# AQ_sensor_GSM.net
KiCad netlist of a schematic drawn in EAGLE
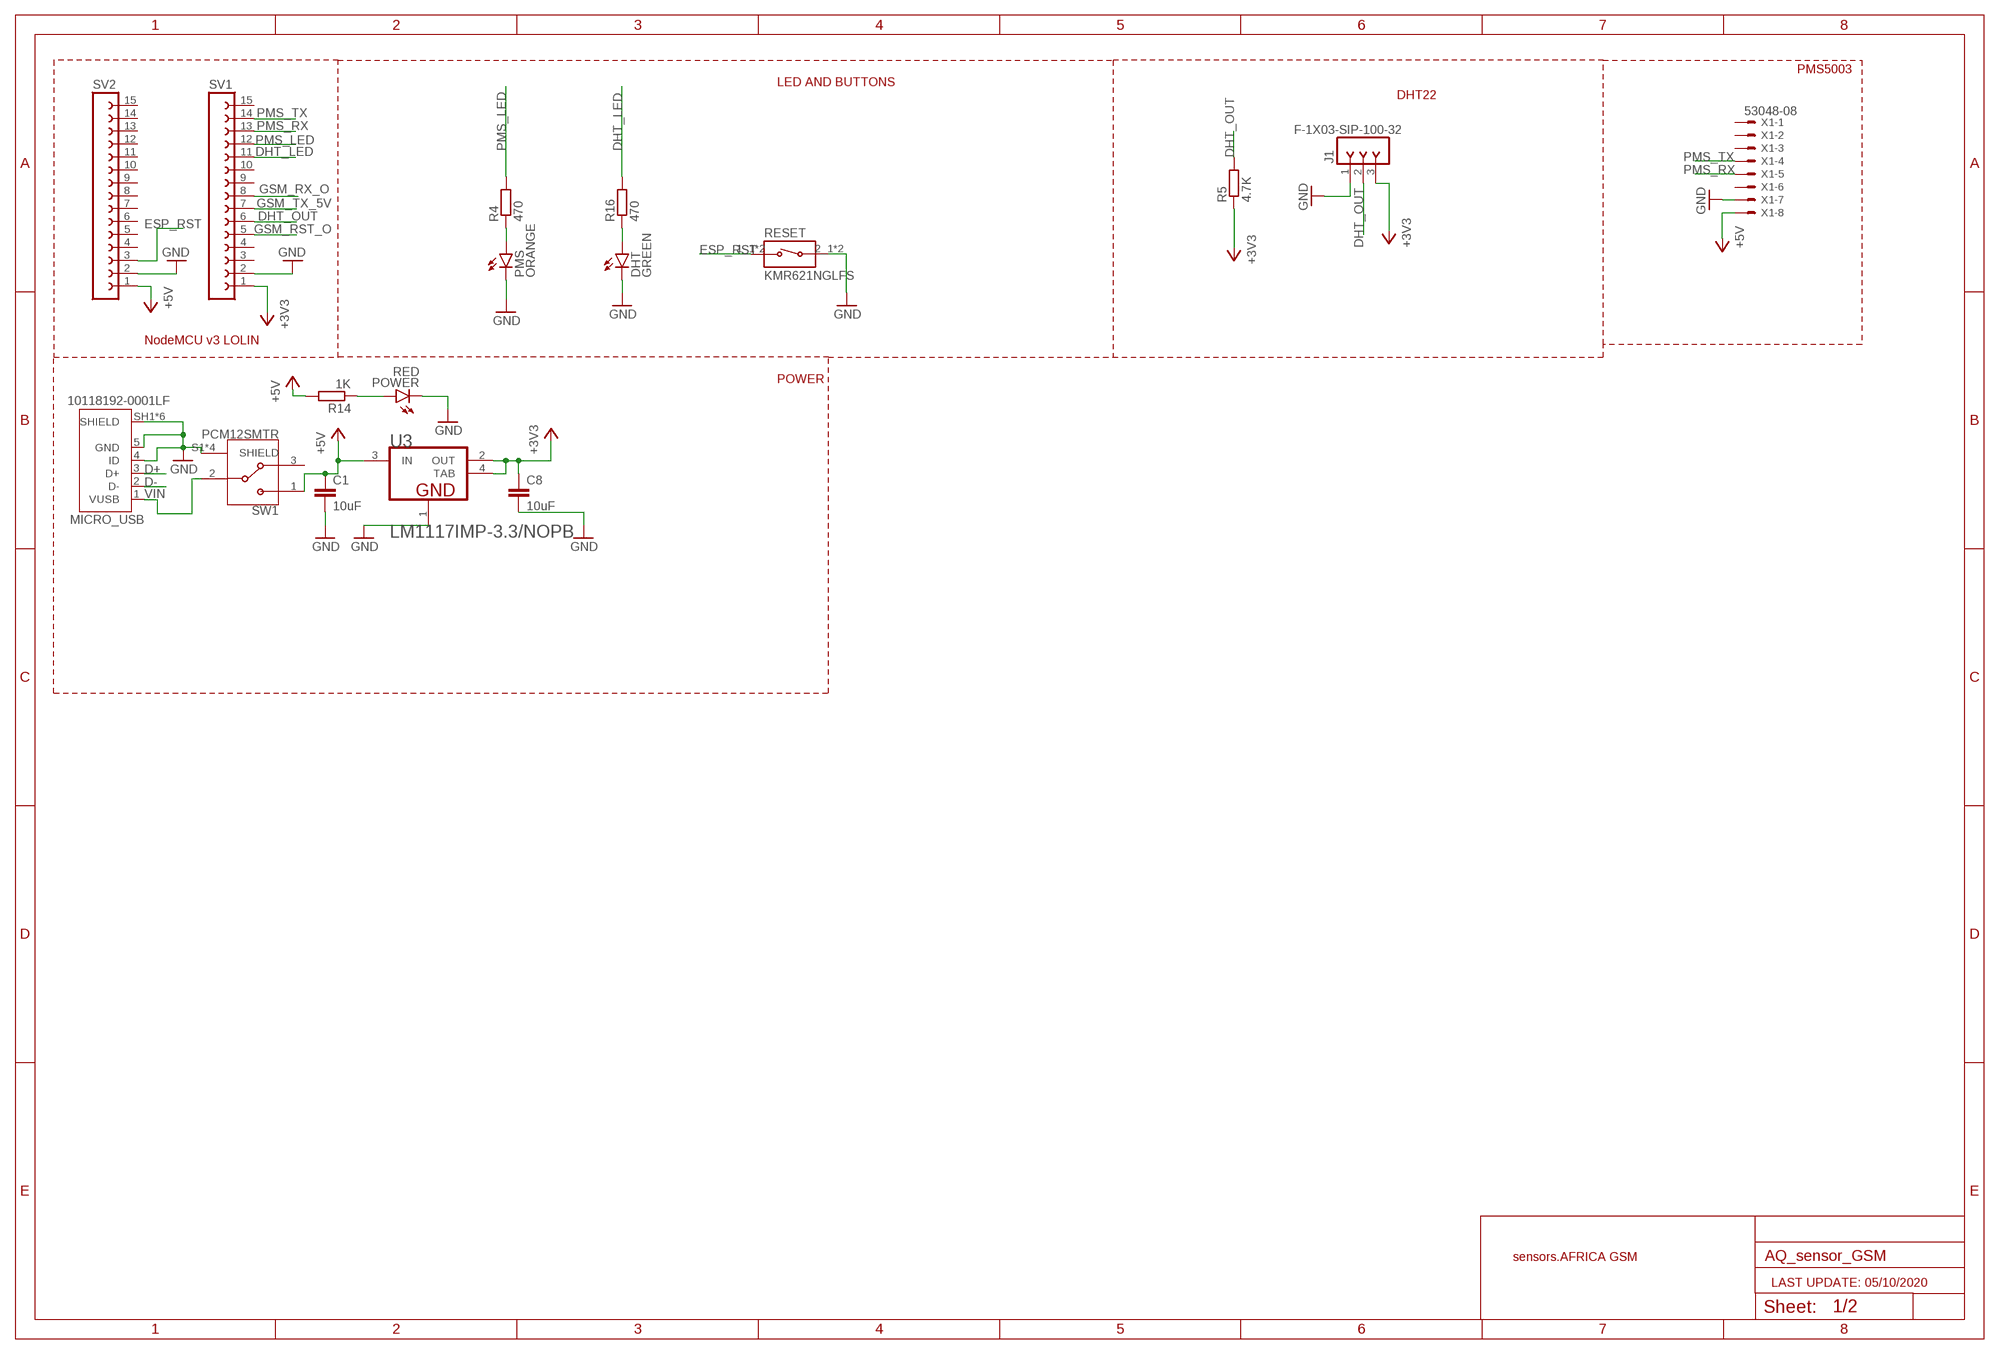
[diagram p0: schematic, sheet 1]
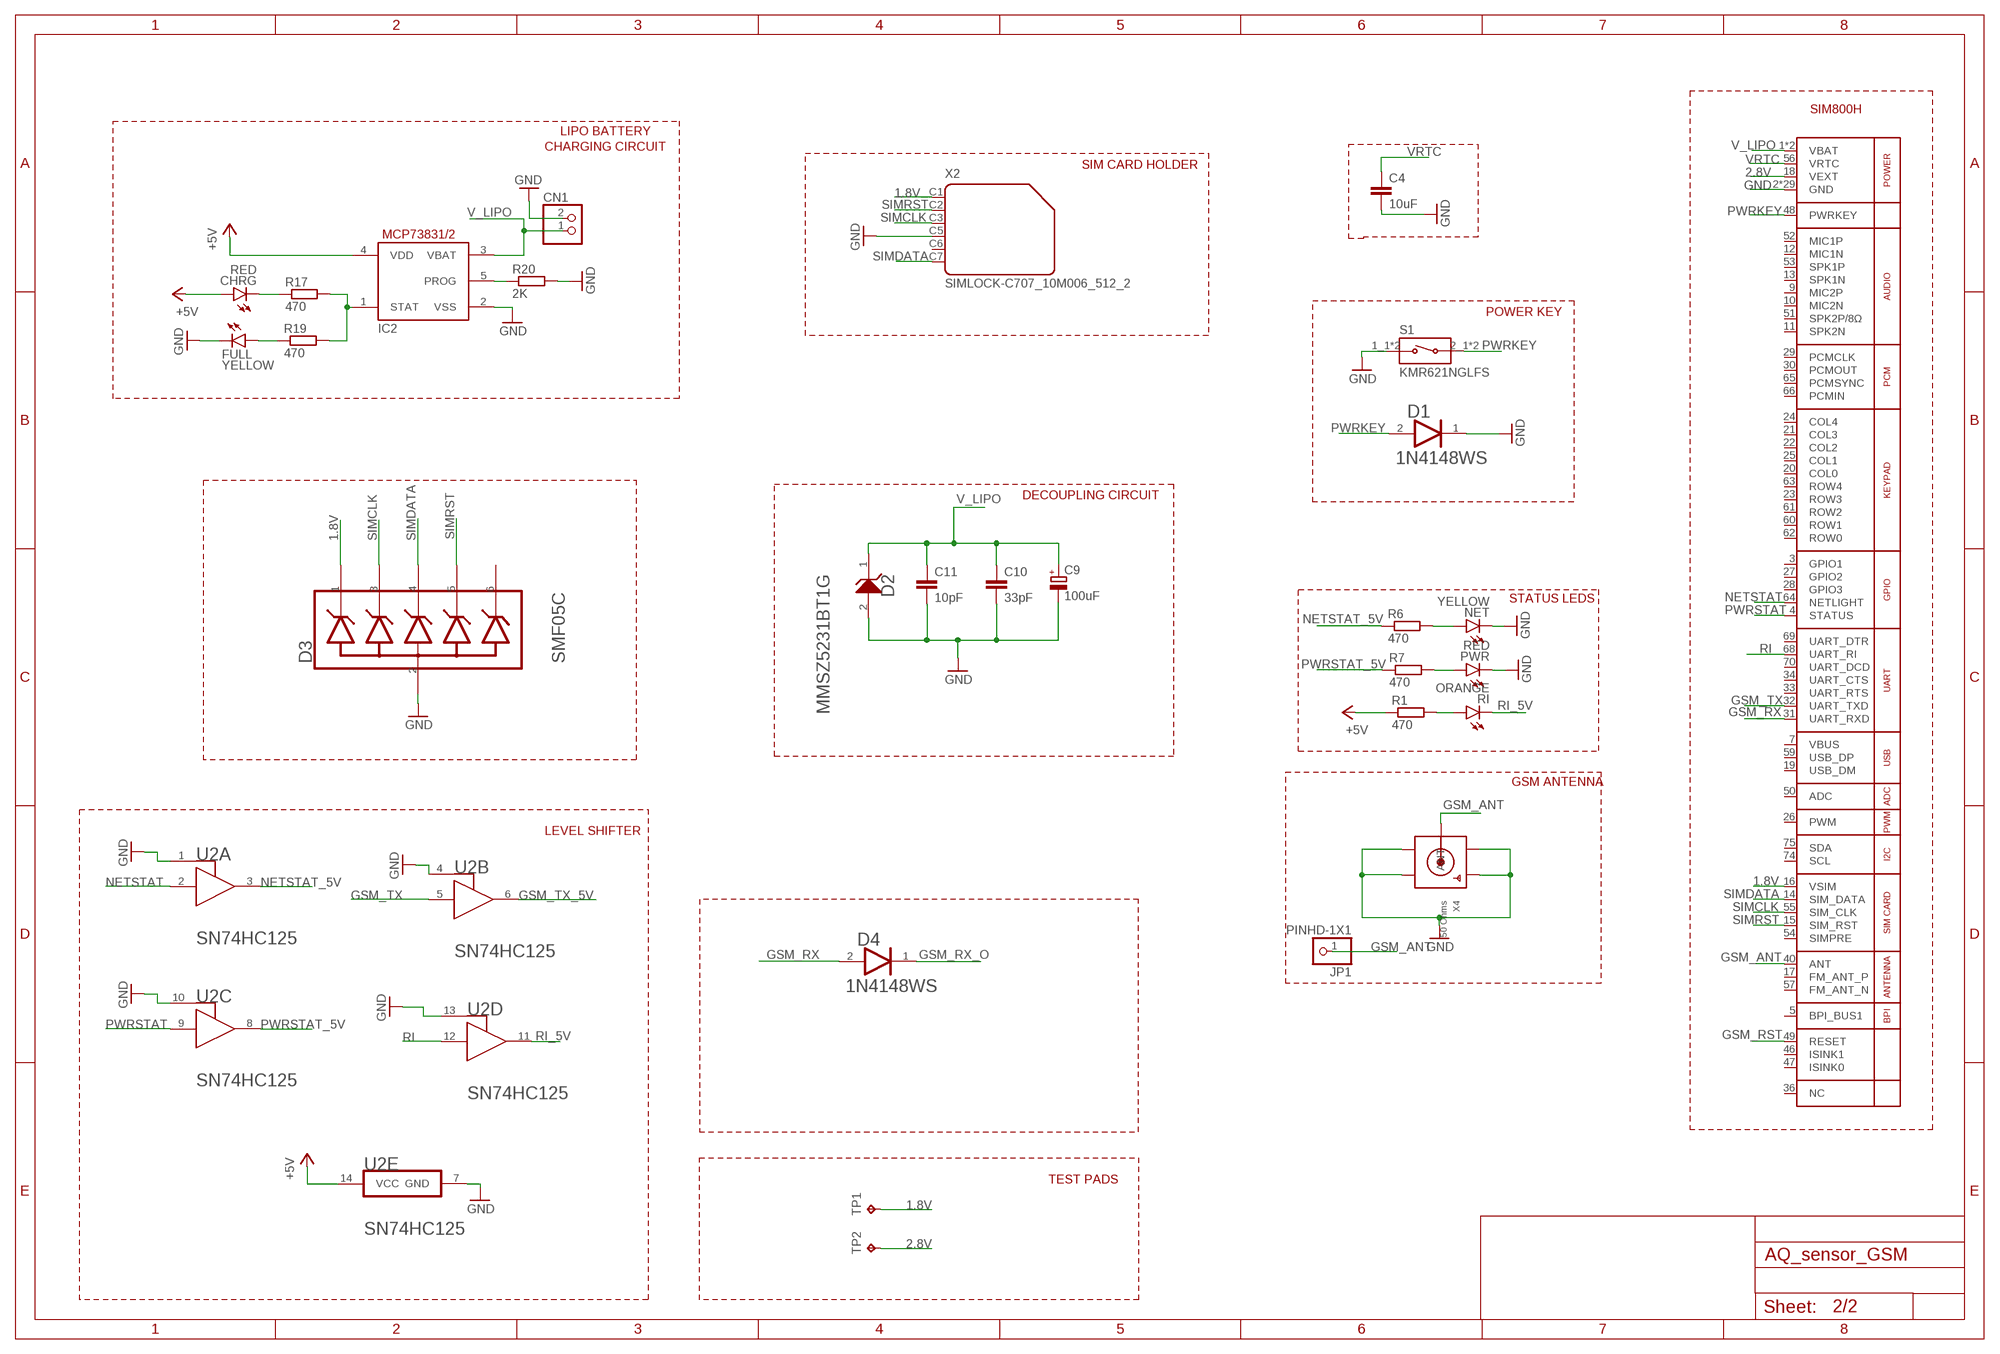
[diagram p1: schematic, sheet 2]

(export (version "E")
  (design (tool "Eeschema 10.0.6"))
  (components
    (comp (ref "C1")
      (value "10uF")
      (footprint "eagle-import:C0603")
      (libsource (lib "eagle-import") (part "C-EUC0603"))
    )
    (comp (ref "C8")
      (value "10uF")
      (footprint "eagle-import:C0603")
      (libsource (lib "eagle-import") (part "C-EUC0603"))
    )
    (comp (ref "DHT")
      (value "GREEN")
      (footprint "eagle-import:CHIP-LED0603")
      (libsource (lib "eagle-import") (part "LEDCHIP-LED0603"))
    )
    (comp (ref "J1")
      (value "F-1X03-SIP-100-32")
      (footprint "eagle-import:SIP-100-03-32")
      (libsource (lib "eagle-import") (part "F-1X03-SIP-100-32"))
    )
    (comp (ref "MICRO_USB")
      (value "10118192-0001LF")
      (footprint "eagle-import:AMPHENOL_10118192-0001LF")
      (fields (field (name "MF") "Amphenol ICC"))
      (libsource (lib "eagle-import") (part "10118192-0001LF"))
    )
    (comp (ref "PMS")
      (value "ORANGE")
      (footprint "eagle-import:CHIP-LED0603")
      (libsource (lib "eagle-import") (part "LEDCHIP-LED0603"))
    )
    (comp (ref "POWER")
      (value "RED")
      (footprint "eagle-import:CHIP-LED0603")
      (libsource (lib "eagle-import") (part "LEDCHIP-LED0603"))
    )
    (comp (ref "R4")
      (value "470")
      (footprint "eagle-import:R0603")
      (libsource (lib "eagle-import") (part "R-EU_R0603"))
    )
    (comp (ref "R5")
      (value "4.7K")
      (footprint "eagle-import:R0603")
      (libsource (lib "eagle-import") (part "R-EU_R0603"))
    )
    (comp (ref "R14")
      (value "1K")
      (footprint "eagle-import:R0603")
      (libsource (lib "eagle-import") (part "R-EU_R0603"))
    )
    (comp (ref "R16")
      (value "470")
      (footprint "eagle-import:R0603")
      (libsource (lib "eagle-import") (part "R-EU_R0603"))
    )
    (comp (ref "RESET")
      (value "KMR621NGLFS")
      (footprint "eagle-import:SW_KMR621NGLFS")
      (fields (field (name "MF") "C&K") (field (name "MP") "KMR621NG LFS"))
      (libsource (lib "eagle-import") (part "KMR621NGLFS_KMR621NGLFS"))
    )
    (comp (ref "SV1")
      (value "FE15-1")
      (footprint "eagle-import:FE15")
      (libsource (lib "eagle-import") (part "FE15-1"))
    )
    (comp (ref "SV2")
      (value "FE15-1")
      (footprint "eagle-import:FE15")
      (libsource (lib "eagle-import") (part "FE15-1"))
    )
    (comp (ref "SW1")
      (value "PCM12SMTR")
      (footprint "eagle-import:SW_PCM12SMTR")
      (fields (field (name "MF") "C&K"))
      (libsource (lib "eagle-import") (part "PCM12SMTR"))
    )
    (comp (ref "U3")
      (value "TEXAS_INSTRUMENTS_LM1117IMP-3.3-NOPBTEXAS_INSTRUMENTS_LM1117IMP-3.3-NOPB_0_0")
      (footprint "eagle-import:TEXAS_INSTRUMENTS_LM1117IMP-3.3-NOPB_0")
      (fields (field (name "MF") "Texas Instruments") (field (name "MPN") "LM1117IMP-3.3/NOPB"))
      (libsource (lib "eagle-import") (part "TEXAS_INSTRUMENTS_LM1117IMP-3.3-NOPBTEXAS_INSTRUMENTS_LM1117IMP-3.3-NOPB_0_0"))
    )
    (comp (ref "X1")
      (value "53048-08")
      (footprint "eagle-import:53048-08")
      (fields (field (name "MF") "WALDOM/MOLEX") (field (name "MPN") "53048-0810"))
      (libsource (lib "eagle-import") (part "53?-08048"))
    )
    (comp (ref "C4")
      (value "10uF")
      (footprint "eagle-import:C0603")
      (libsource (lib "eagle-import") (part "C-EUC0603"))
    )
    (comp (ref "C9")
      (value "100uF")
      (footprint "eagle-import:PANASONIC_D")
      (libsource (lib "eagle-import") (part "CPOL-EUD"))
    )
    (comp (ref "C10")
      (value "33pF")
      (footprint "eagle-import:C0603")
      (libsource (lib "eagle-import") (part "C-EUC0603"))
    )
    (comp (ref "C11")
      (value "10pF")
      (footprint "eagle-import:C0603")
      (libsource (lib "eagle-import") (part "C-EUC0603"))
    )
    (comp (ref "CHRG")
      (value "RED")
      (footprint "eagle-import:CHIP-LED0603")
      (libsource (lib "eagle-import") (part "LEDCHIP-LED0603"))
    )
    (comp (ref "CN1")
      (value "JST_2PIN-SMT-RA")
      (footprint "eagle-import:JST-PH-2-SMT-RA")
      (libsource (lib "eagle-import") (part "JST_2PIN-SMT-RA"))
    )
    (comp (ref "D1")
      (value "ON_SEMI_1N4148WSON_SEMI_1N4148WS_0_0")
      (footprint "eagle-import:ON_SEMI_1N4148WS_0")
      (fields
        (field (name "DIGIKEY_PART_NUMBER") "1N4148WSFSCT-ND")
        (field (name "MF") "ON Semi")
        (field (name "MOUSER_PART_NUMBER") "512-1N4148WS")
      )
      (libsource (lib "eagle-import") (part "ON_SEMI_1N4148WSON_SEMI_1N4148WS_0_0"))
    )
    (comp (ref "D2")
      (value "ON_SEMICONDUCTOR_MMSZ5231BT1GON_SEMICONDUCTOR_MMSZ5231BT1G_0_0")
      (footprint "eagle-import:ON_SEMICONDUCTOR_MMSZ5231BT1G_0")
      (fields (field (name "MF") "On Semiconductor") (field (name "MPN") "MMSZ5231BT1G"))
      (libsource (lib "eagle-import") (part "ON_SEMICONDUCTOR_MMSZ5231BT1GON_SEMICONDUCTOR_MMSZ5231BT1G_0_0"))
    )
    (comp (ref "D3")
      (value "SEMTECH_SMF05CSEMTECH_SMF05C_0_0")
      (footprint "eagle-import:SEMTECH_SMF05C_0")
      (fields
        (field (name "DIGIKEY_PART_NUMBER") "SMF05CCT-ND")
        (field (name "MF") "Semtech")
        (field (name "MOUSER_PART_NUMBER") "947-SMF05C.TCT")
      )
      (libsource (lib "eagle-import") (part "SEMTECH_SMF05CSEMTECH_SMF05C_0_0"))
    )
    (comp (ref "D4")
      (value "ON_SEMI_1N4148WSON_SEMI_1N4148WS_0_0")
      (footprint "eagle-import:ON_SEMI_1N4148WS_0")
      (fields
        (field (name "DIGIKEY_PART_NUMBER") "1N4148WSFSCT-ND")
        (field (name "MF") "ON Semi")
        (field (name "MOUSER_PART_NUMBER") "512-1N4148WS")
      )
      (libsource (lib "eagle-import") (part "ON_SEMI_1N4148WSON_SEMI_1N4148WS_0_0"))
    )
    (comp (ref "FULL")
      (value "YELLOW")
      (footprint "eagle-import:CHIP-LED0603")
      (libsource (lib "eagle-import") (part "LEDCHIP-LED0603"))
    )
    (comp (ref "IC2")
      (value "MCP73831/OT")
      (footprint "eagle-import:SOT23-5L")
      (libsource (lib "eagle-import") (part "MCP73831/OT"))
    )
    (comp (ref "JP1")
      (value "PINHD-1X1")
      (footprint "eagle-import:1X01")
      (fields (field (name "MANUFACTURER") "Generic"))
      (libsource (lib "eagle-import") (part "PINHD-1X1"))
    )
    (comp (ref "NET")
      (value "YELLOW")
      (footprint "eagle-import:CHIP-LED0603")
      (libsource (lib "eagle-import") (part "LEDCHIP-LED0603"))
    )
    (comp (ref "PWR")
      (value "RED")
      (footprint "eagle-import:CHIP-LED0603")
      (libsource (lib "eagle-import") (part "LEDCHIP-LED0603"))
    )
    (comp (ref "R1")
      (value "470")
      (footprint "eagle-import:R0603")
      (libsource (lib "eagle-import") (part "R-EU_R0603"))
    )
    (comp (ref "R6")
      (value "470")
      (footprint "eagle-import:R0603")
      (libsource (lib "eagle-import") (part "R-EU_R0603"))
    )
    (comp (ref "R7")
      (value "470")
      (footprint "eagle-import:R0603")
      (libsource (lib "eagle-import") (part "R-EU_R0603"))
    )
    (comp (ref "R17")
      (value "470")
      (footprint "eagle-import:R0603")
      (libsource (lib "eagle-import") (part "R-EU_R0603"))
    )
    (comp (ref "R19")
      (value "470")
      (footprint "eagle-import:R0603")
      (libsource (lib "eagle-import") (part "R-EU_R0603"))
    )
    (comp (ref "R20")
      (value "2K")
      (footprint "eagle-import:R0603")
      (libsource (lib "eagle-import") (part "R-EU_R0603"))
    )
    (comp (ref "RI")
      (value "ORANGE")
      (footprint "eagle-import:CHIP-LED0603")
      (libsource (lib "eagle-import") (part "LEDCHIP-LED0603"))
    )
    (comp (ref "S1")
      (value "KMR621NGLFS")
      (footprint "eagle-import:SW_KMR621NGLFS")
      (fields (field (name "MF") "C&K") (field (name "MP") "KMR621NG LFS"))
      (libsource (lib "eagle-import") (part "KMR621NGLFS"))
    )
    (comp (ref "TP1")
      (value "TPB1,27")
      (footprint "eagle-import:B1,27")
      (libsource (lib "eagle-import") (part "TPB1,27"))
    )
    (comp (ref "TP2")
      (value "TPB1,27")
      (footprint "eagle-import:B1,27")
      (libsource (lib "eagle-import") (part "TPB1,27"))
    )
    (comp (ref "U1")
      (value "GSM_SIM800L")
      (footprint "eagle-import:SIM800L")
      (libsource (lib "eagle-import") (part "GSM_SIM800L"))
    )
    (comp (ref "U2")
      (value "TEXAS_INSTRUMENTS_SN74HC125TEXAS_INSTRUMENTS_SN74HC125_0_0")
      (footprint "eagle-import:TEXAS_INSTRUMENTS_SN74HC125_0")
      (fields (field (name "MF") "Texas Instruments") (field (name "MPN") "SN74HC125"))
      (libsource (lib "eagle-import") (part "TEXAS_INSTRUMENTS_SN74HC125TEXAS_INSTRUMENTS_SN74HC125_0_0"))
    )
    (comp (ref "X2")
      (value "SIMLOCK-C707_10M006_512_2")
      (footprint "eagle-import:C707_10M006_512_2")
      (libsource (lib "eagle-import") (part "SIMLOCK-C707_10M006_512_2"))
    )
    (comp (ref "X4")
      (value "50 Ohms")
      (footprint "eagle-import:SMA_EDGELAUNCH_UFL")
      (libsource (lib "eagle-import") (part "SMACONNECTOR_EDGE_UFL"))
    )
  )
  (nets
    (net (code "1") (name "+3V3") (class "Default")
      (node (ref "C8") (pin "1") (pinfunction "1_1") (pintype "passive"))
      (node (ref "J1") (pin "3") (pinfunction "3_3") (pintype "passive"))
      (node (ref "R5") (pin "1") (pinfunction "1_1") (pintype "passive"))
      (node (ref "SV1") (pin "1") (pinfunction "1_1") (pintype "passive"))
      (node (ref "U3") (pin "2") (pinfunction "OUT_2") (pintype "power_in"))
      (node (ref "U3") (pin "4") (pinfunction "TAB_4") (pintype "power_in"))
    )
    (net (code "2") (name "+5V") (class "Default")
      (node (ref "C1") (pin "1") (pinfunction "1_1") (pintype "passive"))
      (node (ref "CHRG") (pin "A") (pinfunction "A_A") (pintype "passive"))
      (node (ref "IC2") (pin "4") (pinfunction "VDD_4") (pintype "power_in"))
      (node (ref "R1") (pin "1") (pinfunction "1_1") (pintype "passive"))
      (node (ref "R14") (pin "2") (pinfunction "2_2") (pintype "passive"))
      (node (ref "SV2") (pin "1") (pinfunction "1_1") (pintype "passive"))
      (node (ref "SW1") (pin "1") (pinfunction "1_1") (pintype "passive"))
      (node (ref "U2") (pin "14") (pinfunction "VCC_14") (pintype "power_in"))
      (node (ref "U3") (pin "3") (pinfunction "IN_3") (pintype "power_in"))
      (node (ref "X1") (pin "8") (pinfunction "S_8") (pintype "passive"))
    )
    (net (code "3") (name "1.8V") (class "Default")
      (node (ref "D3") (pin "1") (pinfunction "1_CATHODE_1") (pintype "bidirectional"))
      (node (ref "TP1") (pin "TP") (pinfunction "TP_TP") (pintype "input"))
      (node (ref "U1") (pin "16") (pinfunction "VSIM_16") (pintype "power_in"))
      (node (ref "X2") (pin "C1") (pinfunction "1_C1") (pintype "passive"))
    )
    (net (code "4") (name "2.8V") (class "Default")
      (node (ref "TP2") (pin "TP") (pinfunction "TP_TP") (pintype "input"))
      (node (ref "U1") (pin "18") (pinfunction "VEXT_18") (pintype "power_in"))
    )
    (net (code "5") (name "D+") (class "Default")
      (node (ref "MICRO_USB") (pin "3") (pinfunction "D+_3") (pintype "passive"))
    )
    (net (code "6") (name "D-") (class "Default")
      (node (ref "MICRO_USB") (pin "2") (pinfunction "D-_2") (pintype "passive"))
    )
    (net (code "7") (name "DHT_LED") (class "Default")
      (node (ref "R16") (pin "2") (pinfunction "2_2") (pintype "passive"))
      (node (ref "SV1") (pin "11") (pinfunction "11_11") (pintype "passive"))
    )
    (net (code "8") (name "DHT_OUT") (class "Default")
      (node (ref "J1") (pin "2") (pinfunction "2_2") (pintype "passive"))
      (node (ref "R5") (pin "2") (pinfunction "2_2") (pintype "passive"))
      (node (ref "SV1") (pin "6") (pinfunction "6_6") (pintype "passive"))
    )
    (net (code "9") (name "ESP_RST") (class "Default")
      (node (ref "RESET") (pin "1_1") (pinfunction "1_1_1") (pintype "passive"))
      (node (ref "RESET") (pin "1_2") (pinfunction "1_1_2") (pintype "passive"))
      (node (ref "SV2") (pin "3") (pinfunction "3_3") (pintype "passive"))
    )
    (net (code "10") (name "GND") (class "Default")
      (node (ref "C1") (pin "2") (pinfunction "2_2") (pintype "passive"))
      (node (ref "C10") (pin "2") (pinfunction "2_2") (pintype "passive"))
      (node (ref "C11") (pin "2") (pinfunction "2_2") (pintype "passive"))
      (node (ref "C4") (pin "2") (pinfunction "2_2") (pintype "passive"))
      (node (ref "C8") (pin "2") (pinfunction "2_2") (pintype "passive"))
      (node (ref "C9") (pin "-") (pinfunction "-_-") (pintype "passive"))
      (node (ref "CN1") (pin "2") (pinfunction "1_2") (pintype "passive"))
      (node (ref "D1") (pin "1") (pinfunction "CATHODE_1") (pintype "bidirectional"))
      (node (ref "D2") (pin "2") (pinfunction "A_2") (pintype "passive"))
      (node (ref "D3") (pin "2") (pinfunction "ANODE_2") (pintype "bidirectional"))
      (node (ref "DHT") (pin "C") (pinfunction "C_C") (pintype "passive"))
      (node (ref "FULL") (pin "C") (pinfunction "C_C") (pintype "passive"))
      (node (ref "IC2") (pin "2") (pinfunction "VSS_2") (pintype "power_in"))
      (node (ref "J1") (pin "1") (pinfunction "1_1") (pintype "passive"))
      (node (ref "MICRO_USB") (pin "4") (pinfunction "ID_4") (pintype "passive"))
      (node (ref "MICRO_USB") (pin "5") (pinfunction "GND_5") (pintype "passive"))
      (node (ref "MICRO_USB") (pin "SH1") (pinfunction "SHIELD_SH1") (pintype "passive"))
      (node (ref "MICRO_USB") (pin "SH2") (pinfunction "SHIELD_SH2") (pintype "passive"))
      (node (ref "MICRO_USB") (pin "SH3") (pinfunction "SHIELD_SH3") (pintype "passive"))
      (node (ref "MICRO_USB") (pin "SH4") (pinfunction "SHIELD_SH4") (pintype "passive"))
      (node (ref "MICRO_USB") (pin "SH5") (pinfunction "SHIELD_SH5") (pintype "passive"))
      (node (ref "MICRO_USB") (pin "SH6") (pinfunction "SHIELD_SH6") (pintype "passive"))
      (node (ref "NET") (pin "C") (pinfunction "C_C") (pintype "passive"))
      (node (ref "PMS") (pin "C") (pinfunction "C_C") (pintype "passive"))
      (node (ref "POWER") (pin "C") (pinfunction "C_C") (pintype "passive"))
      (node (ref "PWR") (pin "C") (pinfunction "C_C") (pintype "passive"))
      (node (ref "R20") (pin "2") (pinfunction "2_2") (pintype "passive"))
      (node (ref "RESET") (pin "2_1") (pinfunction "2_2_1") (pintype "passive"))
      (node (ref "RESET") (pin "2_2") (pinfunction "2_2_2") (pintype "passive"))
      (node (ref "S1") (pin "1_1") (pinfunction "1_1_1") (pintype "passive"))
      (node (ref "S1") (pin "1_2") (pinfunction "1_1_2") (pintype "passive"))
      (node (ref "SV1") (pin "2") (pinfunction "2_2") (pintype "passive"))
      (node (ref "SV2") (pin "2") (pinfunction "2_2") (pintype "passive"))
      (node (ref "SW1") (pin "S1") (pinfunction "SHIELD_S1") (pintype "passive"))
      (node (ref "SW1") (pin "S2") (pinfunction "SHIELD_S2") (pintype "passive"))
      (node (ref "SW1") (pin "S3") (pinfunction "SHIELD_S3") (pintype "passive"))
      (node (ref "SW1") (pin "S4") (pinfunction "SHIELD_S4") (pintype "passive"))
      (node (ref "U1") (pin "2") (pinfunction "GND_2") (pintype "power_in"))
      (node (ref "U1") (pin "35") (pinfunction "GND_35") (pintype "power_in"))
      (node (ref "U1") (pin "37") (pinfunction "GND_37") (pintype "power_in"))
      (node (ref "U1") (pin "38") (pinfunction "GND_38") (pintype "power_in"))
      (node (ref "U1") (pin "39") (pinfunction "GND_39") (pintype "power_in"))
      (node (ref "U1") (pin "41") (pinfunction "GND_41") (pintype "power_in"))
      (node (ref "U1") (pin "43") (pinfunction "GND_43") (pintype "power_in"))
      (node (ref "U1") (pin "44") (pinfunction "GND_44") (pintype "power_in"))
      (node (ref "U1") (pin "45") (pinfunction "GND_45") (pintype "power_in"))
      (node (ref "U1") (pin "58") (pinfunction "GND_58") (pintype "power_in"))
      (node (ref "U1") (pin "6") (pinfunction "GND_6") (pintype "power_in"))
      (node (ref "U1") (pin "67") (pinfunction "GND_67") (pintype "power_in"))
      (node (ref "U1") (pin "71") (pinfunction "GND_71") (pintype "power_in"))
      (node (ref "U1") (pin "72") (pinfunction "GND_72") (pintype "power_in"))
      (node (ref "U1") (pin "73") (pinfunction "GND_73") (pintype "power_in"))
      (node (ref "U1") (pin "76") (pinfunction "GND_76") (pintype "power_in"))
      (node (ref "U1") (pin "77") (pinfunction "GND_77") (pintype "power_in"))
      (node (ref "U1") (pin "78") (pinfunction "GND_78") (pintype "power_in"))
      (node (ref "U1") (pin "79") (pinfunction "GND_79") (pintype "power_in"))
      (node (ref "U1") (pin "8") (pinfunction "GND_8") (pintype "power_in"))
      (node (ref "U1") (pin "80") (pinfunction "GND_80") (pintype "power_in"))
      (node (ref "U1") (pin "81") (pinfunction "GND_81") (pintype "power_in"))
      (node (ref "U1") (pin "82") (pinfunction "GND_82") (pintype "power_in"))
      (node (ref "U1") (pin "83") (pinfunction "GND_83") (pintype "power_in"))
      (node (ref "U1") (pin "84") (pinfunction "GND_84") (pintype "power_in"))
      (node (ref "U1") (pin "85") (pinfunction "GND_85") (pintype "power_in"))
      (node (ref "U1") (pin "86") (pinfunction "GND_86") (pintype "power_in"))
      (node (ref "U1") (pin "87") (pinfunction "GND_87") (pintype "power_in"))
      (node (ref "U1") (pin "88") (pinfunction "GND_88") (pintype "power_in"))
      (node (ref "U2") (pin "1") (pinfunction "1_~{OE}_1") (pintype "input"))
      (node (ref "U2") (pin "10") (pinfunction "2_~{OE}_10") (pintype "input"))
      (node (ref "U2") (pin "13") (pinfunction "3_~{OE}_13") (pintype "input"))
      (node (ref "U2") (pin "4") (pinfunction "4_~{OE}_4") (pintype "input"))
      (node (ref "U2") (pin "7") (pinfunction "GND_7") (pintype "power_in"))
      (node (ref "U3") (pin "1") (pinfunction "GND_1") (pintype "power_in"))
      (node (ref "X1") (pin "7") (pinfunction "S_7") (pintype "passive"))
      (node (ref "X2") (pin "C5") (pinfunction "4_C5") (pintype "passive"))
      (node (ref "X4") (pin "GND@1") (pinfunction "GND1_GND@1") (pintype "power_in"))
      (node (ref "X4") (pin "GND@2") (pinfunction "GND2_GND@2") (pintype "power_in"))
      (node (ref "X4") (pin "GND@3") (pinfunction "GND3_GND@3") (pintype "power_in"))
      (node (ref "X4") (pin "GND@4") (pinfunction "GND4_GND@4") (pintype "power_in"))
    )
    (net (code "11") (name "GSM_ANT") (class "Default")
      (node (ref "JP1") (pin "1") (pinfunction "1_1") (pintype "passive"))
      (node (ref "U1") (pin "40") (pinfunction "ANT_40") (pintype "bidirectional"))
      (node (ref "X4") (pin "P") (pinfunction "ANT_P") (pintype "bidirectional"))
    )
    (net (code "12") (name "GSM_RST") (class "Default")
      (node (ref "U1") (pin "49") (pinfunction "RESET_49") (pintype "input"))
    )
    (net (code "13") (name "GSM_RST_O") (class "Default")
      (node (ref "SV1") (pin "5") (pinfunction "5_5") (pintype "passive"))
    )
    (net (code "14") (name "GSM_RX") (class "Default")
      (node (ref "D4") (pin "2") (pinfunction "ANODE_2") (pintype "bidirectional"))
      (node (ref "U1") (pin "31") (pinfunction "UART_RXD_31") (pintype "input"))
    )
    (net (code "15") (name "GSM_RX_O") (class "Default")
      (node (ref "D4") (pin "1") (pinfunction "CATHODE_1") (pintype "bidirectional"))
      (node (ref "SV1") (pin "8") (pinfunction "8_8") (pintype "passive"))
    )
    (net (code "16") (name "GSM_TX") (class "Default")
      (node (ref "U1") (pin "32") (pinfunction "UART_TXD_32") (pintype "output"))
      (node (ref "U2") (pin "5") (pinfunction "2A_5") (pintype "input"))
    )
    (net (code "17") (name "GSM_TX_5V") (class "Default")
      (node (ref "SV1") (pin "7") (pinfunction "7_7") (pintype "passive"))
      (node (ref "U2") (pin "6") (pinfunction "2Y_6") (pintype "tri_state"))
    )
    (net (code "18") (name "NETSTAT") (class "Default")
      (node (ref "U1") (pin "64") (pinfunction "NETLIGHT_64") (pintype "output"))
      (node (ref "U2") (pin "2") (pinfunction "1A_2") (pintype "input"))
    )
    (net (code "19") (name "NETSTAT_5V") (class "Default")
      (node (ref "R6") (pin "1") (pinfunction "1_1") (pintype "passive"))
      (node (ref "U2") (pin "3") (pinfunction "1Y_3") (pintype "tri_state"))
    )
    (net (code "20") (name "Net-(CHRG-PadC)") (class "Default")
      (node (ref "CHRG") (pin "C") (pinfunction "C_C") (pintype "passive"))
      (node (ref "R17") (pin "1") (pinfunction "1_1") (pintype "passive"))
    )
    (net (code "21") (name "Net-(DHT-PadA)") (class "Default")
      (node (ref "DHT") (pin "A") (pinfunction "A_A") (pintype "passive"))
      (node (ref "R16") (pin "1") (pinfunction "1_1") (pintype "passive"))
    )
    (net (code "22") (name "Net-(FULL-PadA)") (class "Default")
      (node (ref "FULL") (pin "A") (pinfunction "A_A") (pintype "passive"))
      (node (ref "R19") (pin "1") (pinfunction "1_1") (pintype "passive"))
    )
    (net (code "23") (name "Net-(IC2-PROG)") (class "Default")
      (node (ref "IC2") (pin "5") (pinfunction "PROG_5") (pintype "input"))
      (node (ref "R20") (pin "1") (pinfunction "1_1") (pintype "passive"))
    )
    (net (code "24") (name "Net-(IC2-STAT)") (class "Default")
      (node (ref "IC2") (pin "1") (pinfunction "STAT_1") (pintype "output"))
      (node (ref "R17") (pin "2") (pinfunction "2_2") (pintype "passive"))
      (node (ref "R19") (pin "2") (pinfunction "2_2") (pintype "passive"))
    )
    (net (code "25") (name "Net-(NET-PadA)") (class "Default")
      (node (ref "NET") (pin "A") (pinfunction "A_A") (pintype "passive"))
      (node (ref "R6") (pin "2") (pinfunction "2_2") (pintype "passive"))
    )
    (net (code "26") (name "Net-(PMS-PadA)") (class "Default")
      (node (ref "PMS") (pin "A") (pinfunction "A_A") (pintype "passive"))
      (node (ref "R4") (pin "1") (pinfunction "1_1") (pintype "passive"))
    )
    (net (code "27") (name "Net-(POWER-PadA)") (class "Default")
      (node (ref "POWER") (pin "A") (pinfunction "A_A") (pintype "passive"))
      (node (ref "R14") (pin "1") (pinfunction "1_1") (pintype "passive"))
    )
    (net (code "28") (name "Net-(PWR-PadA)") (class "Default")
      (node (ref "PWR") (pin "A") (pinfunction "A_A") (pintype "passive"))
      (node (ref "R7") (pin "2") (pinfunction "2_2") (pintype "passive"))
    )
    (net (code "29") (name "Net-(R1-Pad2)") (class "Default")
      (node (ref "R1") (pin "2") (pinfunction "2_2") (pintype "passive"))
      (node (ref "RI") (pin "A") (pinfunction "A_A") (pintype "passive"))
    )
    (net (code "30") (name "PMS_LED") (class "Default")
      (node (ref "R4") (pin "2") (pinfunction "2_2") (pintype "passive"))
      (node (ref "SV1") (pin "12") (pinfunction "12_12") (pintype "passive"))
    )
    (net (code "31") (name "PMS_RX") (class "Default")
      (node (ref "SV1") (pin "13") (pinfunction "13_13") (pintype "passive"))
      (node (ref "X1") (pin "5") (pinfunction "S_5") (pintype "passive"))
    )
    (net (code "32") (name "PMS_TX") (class "Default")
      (node (ref "SV1") (pin "14") (pinfunction "14_14") (pintype "passive"))
      (node (ref "X1") (pin "4") (pinfunction "S_4") (pintype "passive"))
    )
    (net (code "33") (name "PWRKEY") (class "Default")
      (node (ref "D1") (pin "2") (pinfunction "ANODE_2") (pintype "bidirectional"))
      (node (ref "S1") (pin "2_1") (pinfunction "2_2_1") (pintype "passive"))
      (node (ref "S1") (pin "2_2") (pinfunction "2_2_2") (pintype "passive"))
      (node (ref "U1") (pin "48") (pinfunction "PWRKEY_48") (pintype "input"))
    )
    (net (code "34") (name "PWRSTAT") (class "Default")
      (node (ref "U1") (pin "4") (pinfunction "STATUS_4") (pintype "output"))
      (node (ref "U2") (pin "9") (pinfunction "3A_9") (pintype "input"))
    )
    (net (code "35") (name "PWRSTAT_5V") (class "Default")
      (node (ref "R7") (pin "1") (pinfunction "1_1") (pintype "passive"))
      (node (ref "U2") (pin "8") (pinfunction "3Y_8") (pintype "tri_state"))
    )
    (net (code "36") (name "RI") (class "Default")
      (node (ref "U1") (pin "68") (pinfunction "UART_RI_68") (pintype "output"))
      (node (ref "U2") (pin "12") (pinfunction "4A_12") (pintype "input"))
    )
    (net (code "37") (name "RI_5V") (class "Default")
      (node (ref "RI") (pin "C") (pinfunction "C_C") (pintype "passive"))
      (node (ref "U2") (pin "11") (pinfunction "4Y_11") (pintype "tri_state"))
    )
    (net (code "38") (name "SIMCLK") (class "Default")
      (node (ref "D3") (pin "3") (pinfunction "2_CATHODE_3") (pintype "bidirectional"))
      (node (ref "U1") (pin "55") (pinfunction "SIM_CLK_55") (pintype "output"))
      (node (ref "X2") (pin "C3") (pinfunction "3_C3") (pintype "passive"))
    )
    (net (code "39") (name "SIMDATA") (class "Default")
      (node (ref "D3") (pin "4") (pinfunction "3_CATHODE_4") (pintype "bidirectional"))
      (node (ref "U1") (pin "14") (pinfunction "SIM_DATA_14") (pintype "bidirectional"))
      (node (ref "X2") (pin "C7") (pinfunction "6_C7") (pintype "passive"))
    )
    (net (code "40") (name "SIMRST") (class "Default")
      (node (ref "D3") (pin "5") (pinfunction "4_CATHODE_5") (pintype "bidirectional"))
      (node (ref "U1") (pin "15") (pinfunction "SIM_RST_15") (pintype "output"))
      (node (ref "X2") (pin "C2") (pinfunction "2_C2") (pintype "passive"))
    )
    (net (code "41") (name "VBUS") (class "Default")
      (node (ref "U1") (pin "7") (pinfunction "VBUS_7") (pintype "power_in"))
    )
    (net (code "42") (name "VIN") (class "Default")
      (node (ref "MICRO_USB") (pin "1") (pinfunction "VUSB_1") (pintype "passive"))
      (node (ref "SW1") (pin "2") (pinfunction "2_2") (pintype "passive"))
    )
    (net (code "43") (name "VRTC") (class "Default")
      (node (ref "C4") (pin "1") (pinfunction "1_1") (pintype "passive"))
      (node (ref "U1") (pin "56") (pinfunction "VRTC_56") (pintype "power_in"))
    )
    (net (code "44") (name "V_LIPO") (class "Default")
      (node (ref "C10") (pin "1") (pinfunction "1_1") (pintype "passive"))
      (node (ref "C11") (pin "1") (pinfunction "1_1") (pintype "passive"))
      (node (ref "C9") (pin "+") (pinfunction "+_+") (pintype "passive"))
      (node (ref "CN1") (pin "1") (pinfunction "2_1") (pintype "passive"))
      (node (ref "D2") (pin "1") (pinfunction "K_1") (pintype "passive"))
      (node (ref "IC2") (pin "3") (pinfunction "VBAT_3") (pintype "bidirectional"))
      (node (ref "U1") (pin "1") (pinfunction "VBAT_1") (pintype "power_in"))
      (node (ref "U1") (pin "42") (pinfunction "VBAT_42") (pintype "power_in"))
    )
    (net (code "45") (name "unconnected-(D3-5_CATHODE-Pad6)") (class "Default")
      (node (ref "D3") (pin "6") (pinfunction "5_CATHODE_6") (pintype "bidirectional"))
    )
    (net (code "46") (name "unconnected-(SV1-Pad3)") (class "Default")
      (node (ref "SV1") (pin "3") (pinfunction "3_3") (pintype "passive"))
    )
    (net (code "47") (name "unconnected-(SV1-Pad4)") (class "Default")
      (node (ref "SV1") (pin "4") (pinfunction "4_4") (pintype "passive"))
    )
    (net (code "48") (name "unconnected-(SV1-Pad9)") (class "Default")
      (node (ref "SV1") (pin "9") (pinfunction "9_9") (pintype "passive"))
    )
    (net (code "49") (name "unconnected-(SV1-Pad10)") (class "Default")
      (node (ref "SV1") (pin "10") (pinfunction "10_10") (pintype "passive"))
    )
    (net (code "50") (name "unconnected-(SV1-Pad15)") (class "Default")
      (node (ref "SV1") (pin "15") (pinfunction "15_15") (pintype "passive"))
    )
    (net (code "51") (name "unconnected-(SV2-Pad4)") (class "Default")
      (node (ref "SV2") (pin "4") (pinfunction "4_4") (pintype "passive"))
    )
    (net (code "52") (name "unconnected-(SV2-Pad5)") (class "Default")
      (node (ref "SV2") (pin "5") (pinfunction "5_5") (pintype "passive"))
    )
    (net (code "53") (name "unconnected-(SV2-Pad6)") (class "Default")
      (node (ref "SV2") (pin "6") (pinfunction "6_6") (pintype "passive"))
    )
    (net (code "54") (name "unconnected-(SV2-Pad7)") (class "Default")
      (node (ref "SV2") (pin "7") (pinfunction "7_7") (pintype "passive"))
    )
    (net (code "55") (name "unconnected-(SV2-Pad8)") (class "Default")
      (node (ref "SV2") (pin "8") (pinfunction "8_8") (pintype "passive"))
    )
    (net (code "56") (name "unconnected-(SV2-Pad9)") (class "Default")
      (node (ref "SV2") (pin "9") (pinfunction "9_9") (pintype "passive"))
    )
    (net (code "57") (name "unconnected-(SV2-Pad10)") (class "Default")
      (node (ref "SV2") (pin "10") (pinfunction "10_10") (pintype "passive"))
    )
    (net (code "58") (name "unconnected-(SV2-Pad11)") (class "Default")
      (node (ref "SV2") (pin "11") (pinfunction "11_11") (pintype "passive"))
    )
    (net (code "59") (name "unconnected-(SV2-Pad12)") (class "Default")
      (node (ref "SV2") (pin "12") (pinfunction "12_12") (pintype "passive"))
    )
    (net (code "60") (name "unconnected-(SV2-Pad13)") (class "Default")
      (node (ref "SV2") (pin "13") (pinfunction "13_13") (pintype "passive"))
    )
    (net (code "61") (name "unconnected-(SV2-Pad14)") (class "Default")
      (node (ref "SV2") (pin "14") (pinfunction "14_14") (pintype "passive"))
    )
    (net (code "62") (name "unconnected-(SV2-Pad15)") (class "Default")
      (node (ref "SV2") (pin "15") (pinfunction "15_15") (pintype "passive"))
    )
    (net (code "63") (name "unconnected-(SW1-Pad3)") (class "Default")
      (node (ref "SW1") (pin "3") (pinfunction "3_3") (pintype "passive"))
    )
    (net (code "64") (name "unconnected-(U1-ADC-Pad50)") (class "Default")
      (node (ref "U1") (pin "50") (pinfunction "ADC_50") (pintype "input"))
    )
    (net (code "65") (name "unconnected-(U1-BPI_BUS1-Pad5)") (class "Default")
      (node (ref "U1") (pin "5") (pinfunction "BPI_BUS1_5") (pintype "output"))
    )
    (net (code "66") (name "unconnected-(U1-COL0-Pad20)") (class "Default")
      (node (ref "U1") (pin "20") (pinfunction "COL0_20") (pintype "bidirectional"))
    )
    (net (code "67") (name "unconnected-(U1-COL1-Pad25)") (class "Default")
      (node (ref "U1") (pin "25") (pinfunction "COL1_25") (pintype "bidirectional"))
    )
    (net (code "68") (name "unconnected-(U1-COL2-Pad22)") (class "Default")
      (node (ref "U1") (pin "22") (pinfunction "COL2_22") (pintype "bidirectional"))
    )
    (net (code "69") (name "unconnected-(U1-COL3-Pad21)") (class "Default")
      (node (ref "U1") (pin "21") (pinfunction "COL3_21") (pintype "bidirectional"))
    )
    (net (code "70") (name "unconnected-(U1-COL4-Pad24)") (class "Default")
      (node (ref "U1") (pin "24") (pinfunction "COL4_24") (pintype "bidirectional"))
    )
    (net (code "71") (name "unconnected-(U1-FM_ANT_N-Pad57)") (class "Default")
      (node (ref "U1") (pin "57") (pinfunction "FM_ANT_N_57") (pintype "bidirectional"))
    )
    (net (code "72") (name "unconnected-(U1-FM_ANT_P-Pad17)") (class "Default")
      (node (ref "U1") (pin "17") (pinfunction "FM_ANT_P_17") (pintype "bidirectional"))
    )
    (net (code "73") (name "unconnected-(U1-GPIO1-Pad3)") (class "Default")
      (node (ref "U1") (pin "3") (pinfunction "GPIO1_3") (pintype "bidirectional"))
    )
    (net (code "74") (name "unconnected-(U1-GPIO2-Pad27)") (class "Default")
      (node (ref "U1") (pin "27") (pinfunction "GPIO2_27") (pintype "bidirectional"))
    )
    (net (code "75") (name "unconnected-(U1-GPIO3-Pad28)") (class "Default")
      (node (ref "U1") (pin "28") (pinfunction "GPIO3_28") (pintype "bidirectional"))
    )
    (net (code "76") (name "unconnected-(U1-ISINK0-Pad47)") (class "Default")
      (node (ref "U1") (pin "47") (pinfunction "ISINK0_47") (pintype "input"))
    )
    (net (code "77") (name "unconnected-(U1-ISINK1-Pad46)") (class "Default")
      (node (ref "U1") (pin "46") (pinfunction "ISINK1_46") (pintype "input"))
    )
    (net (code "78") (name "unconnected-(U1-MIC1N-Pad12)") (class "Default")
      (node (ref "U1") (pin "12") (pinfunction "MIC1N_12") (pintype "input"))
    )
    (net (code "79") (name "unconnected-(U1-MIC1P-Pad52)") (class "Default")
      (node (ref "U1") (pin "52") (pinfunction "MIC1P_52") (pintype "input"))
    )
    (net (code "80") (name "unconnected-(U1-MIC2N-Pad10)") (class "Default")
      (node (ref "U1") (pin "10") (pinfunction "MIC2N_10") (pintype "input"))
    )
    (net (code "81") (name "unconnected-(U1-MIC2P-Pad9)") (class "Default")
      (node (ref "U1") (pin "9") (pinfunction "MIC2P_9") (pintype "input"))
    )
    (net (code "82") (name "unconnected-(U1-NC-Pad36)") (class "Default")
      (node (ref "U1") (pin "36") (pinfunction "NC_36") (pintype "no_connect"))
    )
    (net (code "83") (name "unconnected-(U1-PCMCLK-Pad29)") (class "Default")
      (node (ref "U1") (pin "29") (pinfunction "PCMCLK_29") (pintype "output"))
    )
    (net (code "84") (name "unconnected-(U1-PCMIN-Pad66)") (class "Default")
      (node (ref "U1") (pin "66") (pinfunction "PCMIN_66") (pintype "input"))
    )
    (net (code "85") (name "unconnected-(U1-PCMOUT-Pad30)") (class "Default")
      (node (ref "U1") (pin "30") (pinfunction "PCMOUT_30") (pintype "output"))
    )
    (net (code "86") (name "unconnected-(U1-PCMSYNC-Pad65)") (class "Default")
      (node (ref "U1") (pin "65") (pinfunction "PCMSYNC_65") (pintype "output"))
    )
    (net (code "87") (name "unconnected-(U1-PWM-Pad26)") (class "Default")
      (node (ref "U1") (pin "26") (pinfunction "PWM_26") (pintype "output"))
    )
    (net (code "88") (name "unconnected-(U1-ROW0-Pad62)") (class "Default")
      (node (ref "U1") (pin "62") (pinfunction "ROW0_62") (pintype "bidirectional"))
    )
    (net (code "89") (name "unconnected-(U1-ROW1-Pad60)") (class "Default")
      (node (ref "U1") (pin "60") (pinfunction "ROW1_60") (pintype "bidirectional"))
    )
    (net (code "90") (name "unconnected-(U1-ROW2-Pad61)") (class "Default")
      (node (ref "U1") (pin "61") (pinfunction "ROW2_61") (pintype "bidirectional"))
    )
    (net (code "91") (name "unconnected-(U1-ROW3-Pad23)") (class "Default")
      (node (ref "U1") (pin "23") (pinfunction "ROW3_23") (pintype "bidirectional"))
    )
    (net (code "92") (name "unconnected-(U1-ROW4-Pad63)") (class "Default")
      (node (ref "U1") (pin "63") (pinfunction "ROW4_63") (pintype "bidirectional"))
    )
    (net (code "93") (name "unconnected-(U1-SCL-Pad74)") (class "Default")
      (node (ref "U1") (pin "74") (pinfunction "SCL_74") (pintype "bidirectional"))
    )
    (net (code "94") (name "unconnected-(U1-SDA-Pad75)") (class "Default")
      (node (ref "U1") (pin "75") (pinfunction "SDA_75") (pintype "bidirectional"))
    )
    (net (code "95") (name "unconnected-(U1-SIMPRE-Pad54)") (class "Default")
      (node (ref "U1") (pin "54") (pinfunction "SIMPRE_54") (pintype "input"))
    )
    (net (code "96") (name "unconnected-(U1-SPK1N-Pad13)") (class "Default")
      (node (ref "U1") (pin "13") (pinfunction "SPK1N_13") (pintype "output"))
    )
    (net (code "97") (name "unconnected-(U1-SPK1P-Pad53)") (class "Default")
      (node (ref "U1") (pin "53") (pinfunction "SPK1P_53") (pintype "output"))
    )
    (net (code "98") (name "unconnected-(U1-SPK2N-Pad11)") (class "Default")
      (node (ref "U1") (pin "11") (pinfunction "SPK2N_11") (pintype "output"))
    )
    (net (code "99") (name "unconnected-(U1-SPK2P{slash}8Ω-Pad51)") (class "Default")
      (node (ref "U1") (pin "51") (pinfunction "SPK2P/8Ω_51") (pintype "output"))
    )
    (net (code "100") (name "unconnected-(U1-UART_CTS-Pad34)") (class "Default")
      (node (ref "U1") (pin "34") (pinfunction "UART_CTS_34") (pintype "output"))
    )
    (net (code "101") (name "unconnected-(U1-UART_DCD-Pad70)") (class "Default")
      (node (ref "U1") (pin "70") (pinfunction "UART_DCD_70") (pintype "input"))
    )
    (net (code "102") (name "unconnected-(U1-UART_DTR-Pad69)") (class "Default")
      (node (ref "U1") (pin "69") (pinfunction "UART_DTR_69") (pintype "input"))
    )
    (net (code "103") (name "unconnected-(U1-UART_RTS-Pad33)") (class "Default")
      (node (ref "U1") (pin "33") (pinfunction "UART_RTS_33") (pintype "input"))
    )
    (net (code "104") (name "unconnected-(U1-USB_DM-Pad19)") (class "Default")
      (node (ref "U1") (pin "19") (pinfunction "USB_DM_19") (pintype "bidirectional"))
    )
    (net (code "105") (name "unconnected-(U1-USB_DP-Pad59)") (class "Default")
      (node (ref "U1") (pin "59") (pinfunction "USB_DP_59") (pintype "bidirectional"))
    )
    (net (code "106") (name "unconnected-(X1A-S-Pad1)") (class "Default")
      (node (ref "X1") (pin "1") (pinfunction "S_1") (pintype "passive"))
    )
    (net (code "107") (name "unconnected-(X1B-S-Pad2)") (class "Default")
      (node (ref "X1") (pin "2") (pinfunction "S_2") (pintype "passive"))
    )
    (net (code "108") (name "unconnected-(X1C-S-Pad3)") (class "Default")
      (node (ref "X1") (pin "3") (pinfunction "S_3") (pintype "passive"))
    )
    (net (code "109") (name "unconnected-(X1F-S-Pad6)") (class "Default")
      (node (ref "X1") (pin "6") (pinfunction "S_6") (pintype "passive"))
    )
    (net (code "110") (name "unconnected-(X2-5-PadC6)") (class "Default")
      (node (ref "X2") (pin "C6") (pinfunction "5_C6") (pintype "passive"))
    )
  )
)
